# SCH_12-volt-power-Altium.net
KiCad netlist of a schematic drawn in Altium Designer
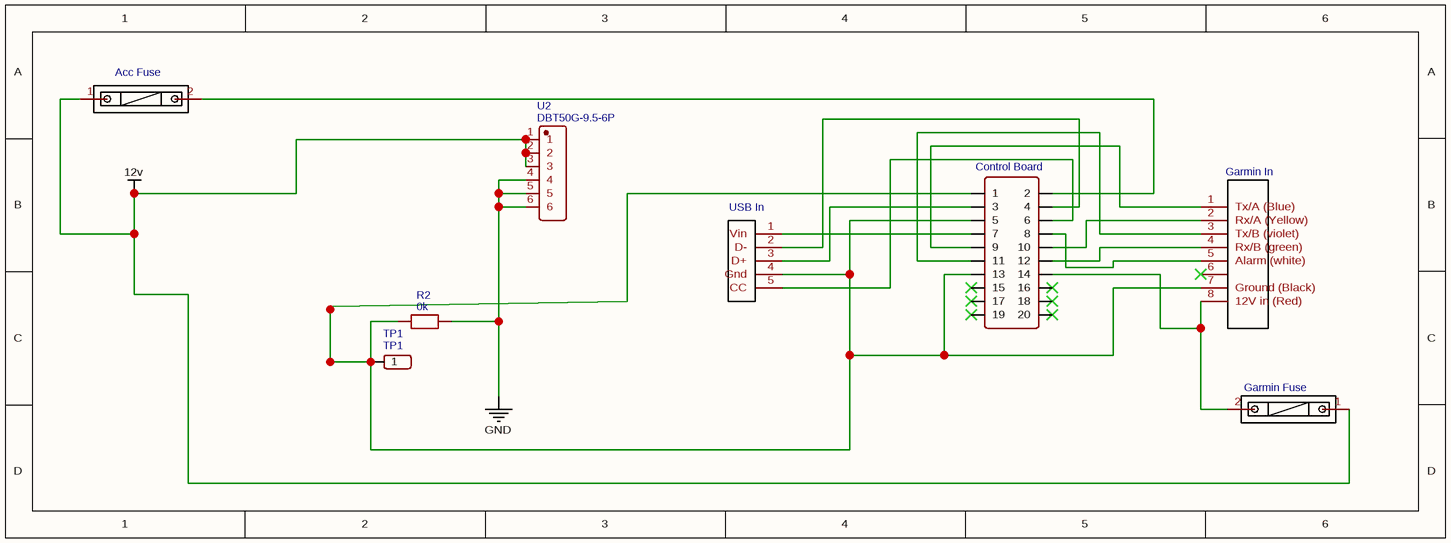
[diagram p0: SCH_12-volt-power-Altium.schdoc]

(export (version "E")
  (design (tool "Eeschema 10.0.6"))
  (components
    (comp (ref "ACC-FUSE-5X20=BLX-ATYPE-FUSE-HOLDER")
      (value "Acc Fuse")
      (fields
        (field (name "MANUFACTURER PART") "5x20 BLX-A型 保险丝支架 XC-7")
        (field (name "MANUFACTURER") "xcfuse(旭程)")
      )
      (libsource (lib "altium-import") (part "root_0_Acc Fuse_"))
    )
    (comp (ref "BUTTON_LED1")
      (value "Control Board")
      (fields (field (name "CONTRIBUTOR") "LCEDA_Lib"))
      (libsource (lib "altium-import") (part "root_0_Control Board_"))
    )
    (comp (ref "GARMIN-FUSE-5X20-BLX-ATYPE-FUSE-HOLDER")
      (value "Garmin Fuse")
      (fields
        (field (name "MANUFACTURER PART") "5x20 BLX-A型 保险丝支架 XC-7")
        (field (name "MANUFACTURER") "xcfuse(旭程)")
      )
      (libsource (lib "altium-import") (part "root_2_Garmin Fuse_"))
    )
    (comp (ref "GARMIN-GPS")
      (value "Garmin In")
      (fields (field (name "MANUFACTURER") "Waveshare") (field (name "CONTRIBUTOR") "Robciog1968"))
      (libsource (lib "altium-import") (part "root_3_Garmin In_"))
    )
    (comp (ref "R2")
      (value "0k")
      (fields (field (name "CONTRIBUTOR") "LCEDA_Lib"))
      (libsource (lib "altium-import") (part "root_0_0k_"))
    )
    (comp (ref "TP1")
      (value "TP1")
      (fields (field (name "CONTRIBUTOR") "LCEDA_Lib"))
      (libsource (lib "altium-import") (part "root_0_TP1_"))
    )
    (comp (ref "U2")
      (value "DBT50G-9.5-6P")
      (fields
        (field (name "MANUFACTURER") "DORABO(地博电气)")
        (field (name "MANUFACTURER PART") "DBT50G-9.5-6P-BK-P OGC")
        (field (name "CONTRIBUTOR") "LCSC")
      )
      (libsource (lib "altium-import") (part "root_0_DBT50G-9.5-6P_"))
    )
    (comp (ref "USB-C")
      (value "USB In")
      (fields (field (name "CONTRIBUTOR") "GeMeMe"))
      (libsource (lib "altium-import") (part "root_0_USB In_"))
    )
  )
  (nets
    (net (code "1") (name "12v") (class "Default")
      (node (ref "ACC-FUSE-5X20=BLX-ATYPE-FUSE-HOLDER") (pin "1") (pinfunction "1_1") (pintype "passive"))
      (node (ref "GARMIN-FUSE-5X20-BLX-ATYPE-FUSE-HOLDER") (pin "1") (pinfunction "1_1") (pintype "passive"))
      (node (ref "U2") (pin "1") (pinfunction "1_1") (pintype "passive"))
      (node (ref "U2") (pin "2") (pinfunction "2_2") (pintype "passive"))
      (node (ref "U2") (pin "3") (pinfunction "3_3") (pintype "passive"))
    )
    (net (code "2") (name "GND") (class "Default")
      (node (ref "R2") (pin "2") (pinfunction "2_2") (pintype "passive"))
      (node (ref "U2") (pin "4") (pinfunction "4_4") (pintype "passive"))
      (node (ref "U2") (pin "5") (pinfunction "5_5") (pintype "passive"))
      (node (ref "U2") (pin "6") (pinfunction "6_6") (pintype "passive"))
    )
    (net (code "3") (name "Net-(ACC-FUSE-5X20=BLX-ATYPE-FUSE-HOLDER-Pad2)") (class "Default")
      (node (ref "ACC-FUSE-5X20=BLX-ATYPE-FUSE-HOLDER") (pin "2") (pinfunction "2_2") (pintype "passive"))
      (node (ref "BUTTON_LED1") (pin "2") (pinfunction "2_2") (pintype "passive"))
    )
    (net (code "4") (name "Net-(GARMIN-GPS-12V_in_(Red))") (class "Default")
      (node (ref "BUTTON_LED1") (pin "14") (pinfunction "14_14") (pintype "passive"))
      (node (ref "GARMIN-FUSE-5X20-BLX-ATYPE-FUSE-HOLDER") (pin "2") (pinfunction "2_2") (pintype "passive"))
      (node (ref "GARMIN-GPS") (pin "8") (pinfunction "12V_in_(Red)_8") (pintype "passive"))
    )
    (net (code "5") (name "Net-(GARMIN-GPS-Alarm_(white))") (class "Default")
      (node (ref "BUTTON_LED1") (pin "8") (pinfunction "8_8") (pintype "passive"))
      (node (ref "GARMIN-GPS") (pin "5") (pinfunction "Alarm_(white)_5") (pintype "passive"))
    )
    (net (code "6") (name "Net-(GARMIN-GPS-Ground_(Black))") (class "Default")
      (node (ref "BUTTON_LED1") (pin "1") (pinfunction "1_1") (pintype "passive"))
      (node (ref "BUTTON_LED1") (pin "13") (pinfunction "13_13") (pintype "passive"))
      (node (ref "BUTTON_LED1") (pin "5") (pinfunction "5_5") (pintype "passive"))
      (node (ref "GARMIN-GPS") (pin "7") (pinfunction "Ground_(Black)_7") (pintype "passive"))
      (node (ref "R2") (pin "1") (pinfunction "1_1") (pintype "passive"))
      (node (ref "TP1") (pin "1") (pinfunction "1_1") (pintype "passive"))
      (node (ref "USB-C") (pin "4") (pinfunction "Gnd_4") (pintype "passive"))
    )
    (net (code "7") (name "Net-(GARMIN-GPS-Rx{slash}A_(Yellow))") (class "Default")
      (node (ref "BUTTON_LED1") (pin "10") (pinfunction "10_10") (pintype "passive"))
      (node (ref "GARMIN-GPS") (pin "2") (pinfunction "Rx/A_(Yellow)_2") (pintype "passive"))
    )
    (net (code "8") (name "Net-(GARMIN-GPS-Rx{slash}B_(green))") (class "Default")
      (node (ref "BUTTON_LED1") (pin "12") (pinfunction "12_12") (pintype "passive"))
      (node (ref "GARMIN-GPS") (pin "4") (pinfunction "Rx/B_(green)_4") (pintype "passive"))
    )
    (net (code "9") (name "Net-(GARMIN-GPS-Tx{slash}A_(Blue))") (class "Default")
      (node (ref "BUTTON_LED1") (pin "9") (pinfunction "9_9") (pintype "passive"))
      (node (ref "GARMIN-GPS") (pin "1") (pinfunction "Tx/A_(Blue)_1") (pintype "passive"))
    )
    (net (code "10") (name "Net-(GARMIN-GPS-Tx{slash}B_(violet))") (class "Default")
      (node (ref "BUTTON_LED1") (pin "11") (pinfunction "11_11") (pintype "passive"))
      (node (ref "GARMIN-GPS") (pin "3") (pinfunction "Tx/B_(violet)_3") (pintype "passive"))
    )
    (net (code "11") (name "Net-(USB-C-CC)") (class "Default")
      (node (ref "BUTTON_LED1") (pin "6") (pinfunction "6_6") (pintype "passive"))
      (node (ref "USB-C") (pin "5") (pinfunction "CC_5") (pintype "passive"))
    )
    (net (code "12") (name "Net-(USB-C-D+)") (class "Default")
      (node (ref "BUTTON_LED1") (pin "3") (pinfunction "3_3") (pintype "passive"))
      (node (ref "USB-C") (pin "3") (pinfunction "D+_3") (pintype "passive"))
    )
    (net (code "13") (name "Net-(USB-C-D-)") (class "Default")
      (node (ref "BUTTON_LED1") (pin "4") (pinfunction "4_4") (pintype "passive"))
      (node (ref "USB-C") (pin "2") (pinfunction "D-_2") (pintype "passive"))
    )
    (net (code "14") (name "Net-(USB-C-Vin)") (class "Default")
      (node (ref "BUTTON_LED1") (pin "7") (pinfunction "7_7") (pintype "passive"))
      (node (ref "USB-C") (pin "1") (pinfunction "Vin_1") (pintype "passive"))
    )
    (net (code "15") (name "unconnected-(BUTTON_LED1-Pad15)") (class "Default")
      (node (ref "BUTTON_LED1") (pin "15") (pinfunction "15_15") (pintype "passive+no_connect"))
    )
    (net (code "16") (name "unconnected-(BUTTON_LED1-Pad16)") (class "Default")
      (node (ref "BUTTON_LED1") (pin "16") (pinfunction "16_16") (pintype "passive+no_connect"))
    )
    (net (code "17") (name "unconnected-(BUTTON_LED1-Pad17)") (class "Default")
      (node (ref "BUTTON_LED1") (pin "17") (pinfunction "17_17") (pintype "passive+no_connect"))
    )
    (net (code "18") (name "unconnected-(BUTTON_LED1-Pad18)") (class "Default")
      (node (ref "BUTTON_LED1") (pin "18") (pinfunction "18_18") (pintype "passive+no_connect"))
    )
    (net (code "19") (name "unconnected-(BUTTON_LED1-Pad19)") (class "Default")
      (node (ref "BUTTON_LED1") (pin "19") (pinfunction "19_19") (pintype "passive+no_connect"))
    )
    (net (code "20") (name "unconnected-(BUTTON_LED1-Pad20)") (class "Default")
      (node (ref "BUTTON_LED1") (pin "20") (pinfunction "20_20") (pintype "passive+no_connect"))
    )
    (net (code "21") (name "unconnected-(GARMIN-GPS-Accessory_On-Pad6)") (class "Default")
      (node (ref "GARMIN-GPS") (pin "6") (pinfunction "Accessory_On_6") (pintype "passive+no_connect"))
    )
  )
)
